# canSlaveV05_testboard.net
KiCad netlist of a schematic drawn in EAGLE
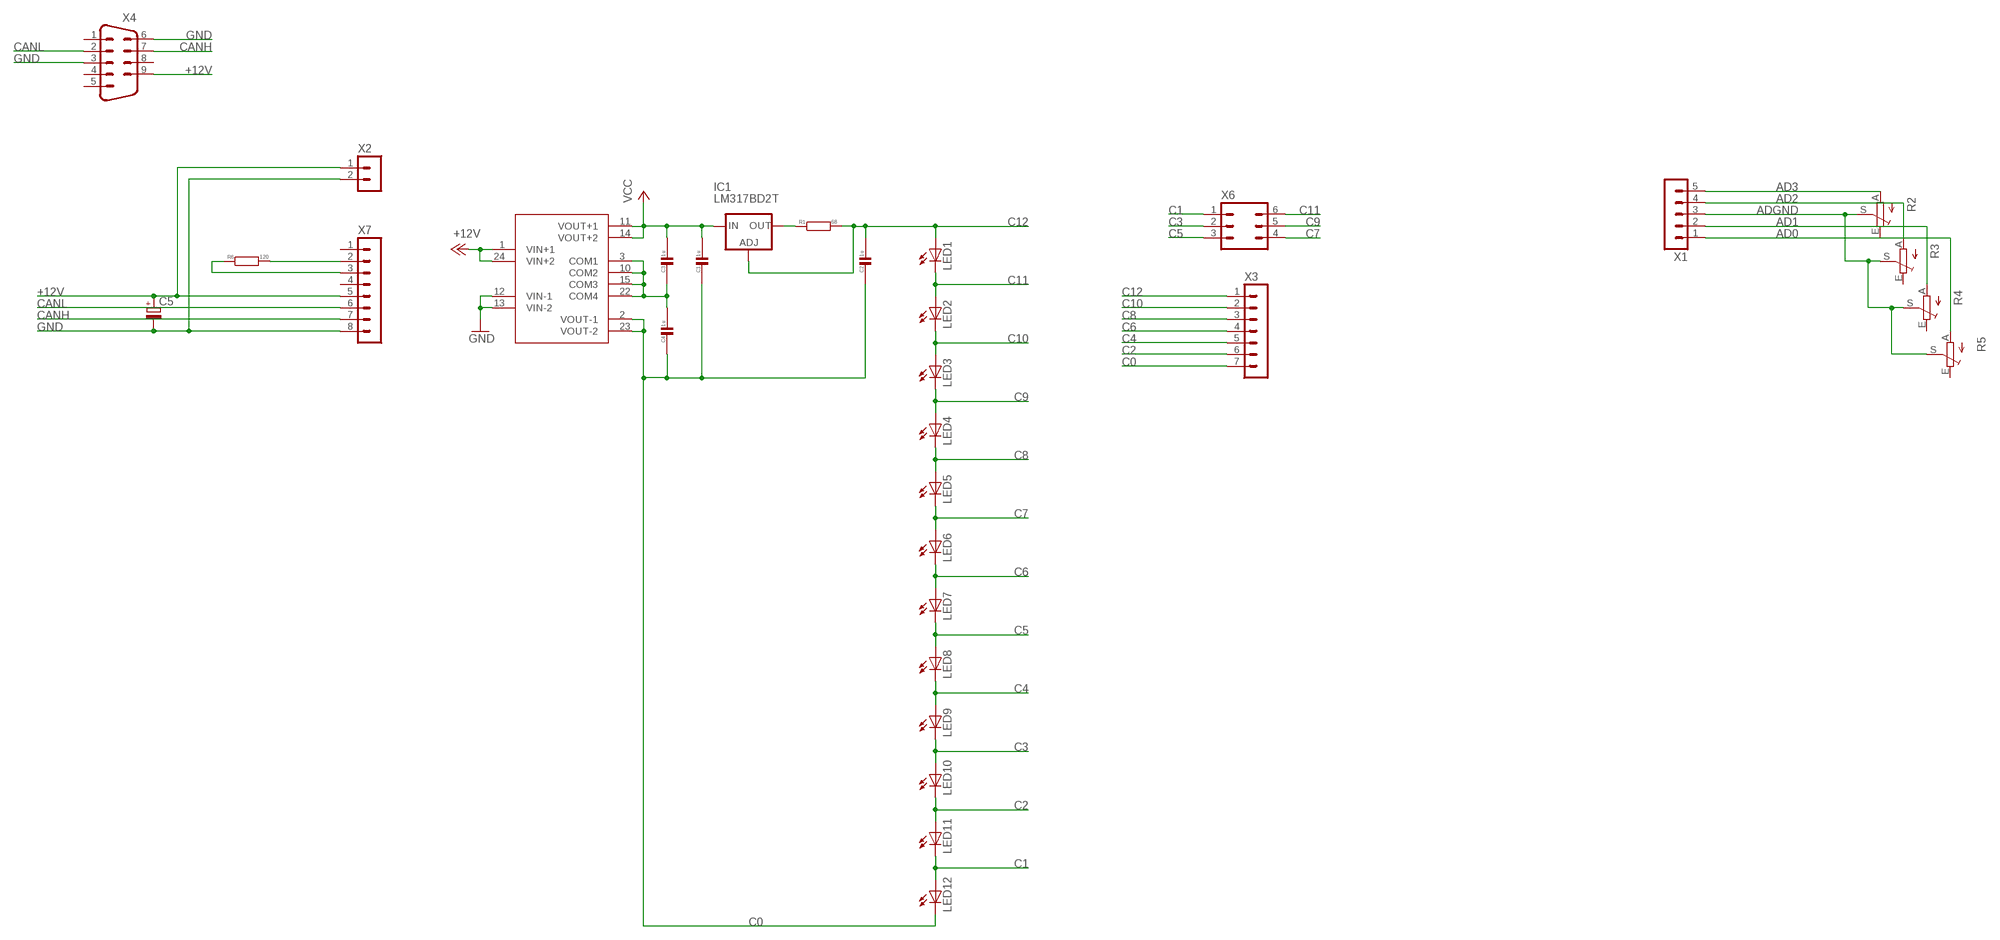
[diagram p0: schematic, sheet 1]

(export (version "E")
  (design (tool "Eeschema 10.0.6"))
  (components
    (comp (ref "C1")
      (value "1u")
      (footprint "eagle-import:C1206")
      (libsource (lib "eagle-import") (part "C1206"))
    )
    (comp (ref "C2")
      (value "1u")
      (footprint "eagle-import:C1206")
      (libsource (lib "eagle-import") (part "C1206"))
    )
    (comp (ref "C3")
      (value "1u")
      (footprint "eagle-import:C1206")
      (libsource (lib "eagle-import") (part "C1206"))
    )
    (comp (ref "C4")
      (value "1u")
      (footprint "eagle-import:C1206")
      (libsource (lib "eagle-import") (part "C1206"))
    )
    (comp (ref "C5")
      (value "CPOL-EUE10-20")
      (footprint "eagle-import:EB20D")
      (libsource (lib "eagle-import") (part "CPOL-EUE10-20"))
    )
    (comp (ref "IC1")
      (value "LM317BD2T")
      (footprint "eagle-import:D2PACK")
      (libsource (lib "eagle-import") (part "LM317?BD2T"))
    )
    (comp (ref "LED1")
      (value "LEDSMT1206")
      (footprint "eagle-import:1206")
      (libsource (lib "eagle-import") (part "LEDSMT1206"))
    )
    (comp (ref "LED2")
      (value "LEDSMT1206")
      (footprint "eagle-import:1206")
      (libsource (lib "eagle-import") (part "LEDSMT1206"))
    )
    (comp (ref "LED3")
      (value "LEDSMT1206")
      (footprint "eagle-import:1206")
      (libsource (lib "eagle-import") (part "LEDSMT1206"))
    )
    (comp (ref "LED4")
      (value "LEDSMT1206")
      (footprint "eagle-import:1206")
      (libsource (lib "eagle-import") (part "LEDSMT1206"))
    )
    (comp (ref "LED5")
      (value "LEDSMT1206")
      (footprint "eagle-import:1206")
      (libsource (lib "eagle-import") (part "LEDSMT1206"))
    )
    (comp (ref "LED6")
      (value "LEDSMT1206")
      (footprint "eagle-import:1206")
      (libsource (lib "eagle-import") (part "LEDSMT1206"))
    )
    (comp (ref "LED7")
      (value "LEDSMT1206")
      (footprint "eagle-import:1206")
      (libsource (lib "eagle-import") (part "LEDSMT1206"))
    )
    (comp (ref "LED8")
      (value "LEDSMT1206")
      (footprint "eagle-import:1206")
      (libsource (lib "eagle-import") (part "LEDSMT1206"))
    )
    (comp (ref "LED9")
      (value "LEDSMT1206")
      (footprint "eagle-import:1206")
      (libsource (lib "eagle-import") (part "LEDSMT1206"))
    )
    (comp (ref "LED10")
      (value "LEDSMT1206")
      (footprint "eagle-import:1206")
      (libsource (lib "eagle-import") (part "LEDSMT1206"))
    )
    (comp (ref "LED11")
      (value "LEDSMT1206")
      (footprint "eagle-import:1206")
      (libsource (lib "eagle-import") (part "LEDSMT1206"))
    )
    (comp (ref "LED12")
      (value "LEDSMT1206")
      (footprint "eagle-import:1206")
      (libsource (lib "eagle-import") (part "LEDSMT1206"))
    )
    (comp (ref "R1")
      (value "68")
      (footprint "eagle-import:R1206")
      (libsource (lib "eagle-import") (part "R1206"))
    )
    (comp (ref "R2")
      (value "TRIM_EU-CIP20C-6MM")
      (footprint "eagle-import:CIP20C-6MM")
      (libsource (lib "eagle-import") (part "TRIM_EU-CIP20C-6MM"))
    )
    (comp (ref "R3")
      (value "TRIM_EU-CIP20C-6MM")
      (footprint "eagle-import:CIP20C-6MM")
      (libsource (lib "eagle-import") (part "TRIM_EU-CIP20C-6MM"))
    )
    (comp (ref "R4")
      (value "TRIM_EU-CIP20C-6MM")
      (footprint "eagle-import:CIP20C-6MM")
      (libsource (lib "eagle-import") (part "TRIM_EU-CIP20C-6MM"))
    )
    (comp (ref "R5")
      (value "TRIM_EU-CIP20C-6MM")
      (footprint "eagle-import:CIP20C-6MM")
      (libsource (lib "eagle-import") (part "TRIM_EU-CIP20C-6MM"))
    )
    (comp (ref "R6")
      (value "120")
      (footprint "eagle-import:R1206")
      (libsource (lib "eagle-import") (part "R1206"))
    )
    (comp (ref "U$1")
      (value "JCB0312D24")
      (footprint "eagle-import:JCB03")
      (libsource (lib "eagle-import") (part "JCB0312D24"))
    )
    (comp (ref "X1")
      (value "HEADER_POS5_43650-0515")
      (footprint "eagle-import:43650-0515")
      (libsource (lib "eagle-import") (part "HEADER_POS5_?43650-0515"))
    )
    (comp (ref "X2")
      (value "HEADER_POS2_43650-0215")
      (footprint "eagle-import:43650-0215")
      (libsource (lib "eagle-import") (part "HEADER_POS2_?43650-0215"))
    )
    (comp (ref "X3")
      (value "HEADER_POS7_43650-0715")
      (footprint "eagle-import:43650-0715")
      (libsource (lib "eagle-import") (part "HEADER_POS7_?43650-0715"))
    )
    (comp (ref "X4")
      (value "M09HP")
      (footprint "eagle-import:M09HP")
      (libsource (lib "eagle-import") (part "M09HP"))
    )
    (comp (ref "X6")
      (value "HEADER_POS6_43650-0615")
      (footprint "eagle-import:43650-0615")
      (libsource (lib "eagle-import") (part "HEADER_POS6_?43650-0615"))
    )
    (comp (ref "X7")
      (value "HEADER_POS8_43045-0812")
      (footprint "eagle-import:43045-0812")
      (libsource (lib "eagle-import") (part "HEADER_POS8_?43045-0812"))
    )
  )
  (nets
    (net (code "1") (name "+12V") (class "Default")
      (node (ref "C5") (pin "+") (pinfunction "+_+") (pintype "passive"))
      (node (ref "U$1") (pin "1") (pinfunction "VIN+1_1") (pintype "bidirectional"))
      (node (ref "U$1") (pin "24") (pinfunction "VIN+2_24") (pintype "bidirectional"))
      (node (ref "X2") (pin "1") (pinfunction "1_1") (pintype "passive"))
      (node (ref "X4") (pin "9") (pinfunction "9_9") (pintype "passive"))
      (node (ref "X7") (pin "5") (pinfunction "5_5") (pintype "passive"))
    )
    (net (code "2") (name "/AD0") (class "Default")
      (node (ref "R5") (pin "A") (pinfunction "A_A") (pintype "passive"))
      (node (ref "X1") (pin "1") (pinfunction "1_1") (pintype "passive"))
    )
    (net (code "3") (name "/AD1") (class "Default")
      (node (ref "R4") (pin "A") (pinfunction "A_A") (pintype "passive"))
      (node (ref "X1") (pin "2") (pinfunction "2_2") (pintype "passive"))
    )
    (net (code "4") (name "/AD2") (class "Default")
      (node (ref "R3") (pin "A") (pinfunction "A_A") (pintype "passive"))
      (node (ref "X1") (pin "4") (pinfunction "4_4") (pintype "passive"))
    )
    (net (code "5") (name "/AD3") (class "Default")
      (node (ref "R2") (pin "A") (pinfunction "A_A") (pintype "passive"))
      (node (ref "X1") (pin "5") (pinfunction "5_5") (pintype "passive"))
    )
    (net (code "6") (name "/ADGND") (class "Default")
      (node (ref "R2") (pin "S") (pinfunction "S_S") (pintype "passive"))
      (node (ref "R3") (pin "S") (pinfunction "S_S") (pintype "passive"))
      (node (ref "R4") (pin "S") (pinfunction "S_S") (pintype "passive"))
      (node (ref "R5") (pin "S") (pinfunction "S_S") (pintype "passive"))
      (node (ref "X1") (pin "3") (pinfunction "3_3") (pintype "passive"))
    )
    (net (code "7") (name "/C0") (class "Default")
      (node (ref "C1") (pin "2") (pinfunction "2_2") (pintype "passive"))
      (node (ref "C2") (pin "2") (pinfunction "2_2") (pintype "passive"))
      (node (ref "C4") (pin "2") (pinfunction "2_2") (pintype "passive"))
      (node (ref "LED12") (pin "C") (pinfunction "C_C") (pintype "passive"))
      (node (ref "U$1") (pin "2") (pinfunction "VOUT-1_2") (pintype "bidirectional"))
      (node (ref "U$1") (pin "23") (pinfunction "VOUT-2_23") (pintype "bidirectional"))
      (node (ref "X3") (pin "7") (pinfunction "7_7") (pintype "passive"))
    )
    (net (code "8") (name "/C1") (class "Default")
      (node (ref "LED11") (pin "C") (pinfunction "C_C") (pintype "passive"))
      (node (ref "LED12") (pin "A") (pinfunction "A_A") (pintype "passive"))
      (node (ref "X6") (pin "1") (pinfunction "1_1") (pintype "passive"))
    )
    (net (code "9") (name "/C2") (class "Default")
      (node (ref "LED10") (pin "C") (pinfunction "C_C") (pintype "passive"))
      (node (ref "LED11") (pin "A") (pinfunction "A_A") (pintype "passive"))
      (node (ref "X3") (pin "6") (pinfunction "6_6") (pintype "passive"))
    )
    (net (code "10") (name "/C3") (class "Default")
      (node (ref "LED10") (pin "A") (pinfunction "A_A") (pintype "passive"))
      (node (ref "LED9") (pin "C") (pinfunction "C_C") (pintype "passive"))
      (node (ref "X6") (pin "2") (pinfunction "2_2") (pintype "passive"))
    )
    (net (code "11") (name "/C4") (class "Default")
      (node (ref "LED8") (pin "C") (pinfunction "C_C") (pintype "passive"))
      (node (ref "LED9") (pin "A") (pinfunction "A_A") (pintype "passive"))
      (node (ref "X3") (pin "5") (pinfunction "5_5") (pintype "passive"))
    )
    (net (code "12") (name "/C5") (class "Default")
      (node (ref "LED7") (pin "C") (pinfunction "C_C") (pintype "passive"))
      (node (ref "LED8") (pin "A") (pinfunction "A_A") (pintype "passive"))
      (node (ref "X6") (pin "3") (pinfunction "3_3") (pintype "passive"))
    )
    (net (code "13") (name "/C6") (class "Default")
      (node (ref "LED6") (pin "C") (pinfunction "C_C") (pintype "passive"))
      (node (ref "LED7") (pin "A") (pinfunction "A_A") (pintype "passive"))
      (node (ref "X3") (pin "4") (pinfunction "4_4") (pintype "passive"))
    )
    (net (code "14") (name "/C7") (class "Default")
      (node (ref "LED5") (pin "C") (pinfunction "C_C") (pintype "passive"))
      (node (ref "LED6") (pin "A") (pinfunction "A_A") (pintype "passive"))
      (node (ref "X6") (pin "4") (pinfunction "4_4") (pintype "passive"))
    )
    (net (code "15") (name "/C8") (class "Default")
      (node (ref "LED4") (pin "C") (pinfunction "C_C") (pintype "passive"))
      (node (ref "LED5") (pin "A") (pinfunction "A_A") (pintype "passive"))
      (node (ref "X3") (pin "3") (pinfunction "3_3") (pintype "passive"))
    )
    (net (code "16") (name "/C9") (class "Default")
      (node (ref "LED3") (pin "C") (pinfunction "C_C") (pintype "passive"))
      (node (ref "LED4") (pin "A") (pinfunction "A_A") (pintype "passive"))
      (node (ref "X6") (pin "5") (pinfunction "5_5") (pintype "passive"))
    )
    (net (code "17") (name "/C10") (class "Default")
      (node (ref "LED2") (pin "C") (pinfunction "C_C") (pintype "passive"))
      (node (ref "LED3") (pin "A") (pinfunction "A_A") (pintype "passive"))
      (node (ref "X3") (pin "2") (pinfunction "2_2") (pintype "passive"))
    )
    (net (code "18") (name "/C11") (class "Default")
      (node (ref "LED1") (pin "C") (pinfunction "C_C") (pintype "passive"))
      (node (ref "LED2") (pin "A") (pinfunction "A_A") (pintype "passive"))
      (node (ref "X6") (pin "6") (pinfunction "6_6") (pintype "passive"))
    )
    (net (code "19") (name "/C12") (class "Default")
      (node (ref "C2") (pin "1") (pinfunction "1_1") (pintype "passive"))
      (node (ref "IC1") (pin "1") (pinfunction "ADJ_1") (pintype "input"))
      (node (ref "LED1") (pin "A") (pinfunction "A_A") (pintype "passive"))
      (node (ref "R1") (pin "2") (pinfunction "2_2") (pintype "passive"))
      (node (ref "X3") (pin "1") (pinfunction "1_1") (pintype "passive"))
    )
    (net (code "20") (name "/CANH") (class "Default")
      (node (ref "X4") (pin "7") (pinfunction "7_7") (pintype "passive"))
      (node (ref "X7") (pin "7") (pinfunction "7_7") (pintype "passive"))
    )
    (net (code "21") (name "/CANL") (class "Default")
      (node (ref "X4") (pin "2") (pinfunction "2_2") (pintype "passive"))
      (node (ref "X7") (pin "6") (pinfunction "6_6") (pintype "passive"))
    )
    (net (code "22") (name "GND") (class "Default")
      (node (ref "C5") (pin "-") (pinfunction "-_-") (pintype "passive"))
      (node (ref "U$1") (pin "12") (pinfunction "VIN-1_12") (pintype "bidirectional"))
      (node (ref "U$1") (pin "13") (pinfunction "VIN-2_13") (pintype "bidirectional"))
      (node (ref "X2") (pin "2") (pinfunction "2_2") (pintype "passive"))
      (node (ref "X4") (pin "3") (pinfunction "3_3") (pintype "passive"))
      (node (ref "X4") (pin "6") (pinfunction "6_6") (pintype "passive"))
      (node (ref "X7") (pin "8") (pinfunction "8_8") (pintype "passive"))
    )
    (net (code "23") (name "Net-(IC1-OUT)") (class "Default")
      (node (ref "IC1") (pin "2") (pinfunction "OUT_2") (pintype "passive"))
      (node (ref "R1") (pin "1") (pinfunction "1_1") (pintype "passive"))
    )
    (net (code "24") (name "Net-(R6-Pad1)") (class "Default")
      (node (ref "R6") (pin "1") (pinfunction "1_1") (pintype "passive"))
      (node (ref "X7") (pin "3") (pinfunction "3_3") (pintype "passive"))
    )
    (net (code "25") (name "Net-(R6-Pad2)") (class "Default")
      (node (ref "R6") (pin "2") (pinfunction "2_2") (pintype "passive"))
      (node (ref "X7") (pin "2") (pinfunction "2_2") (pintype "passive"))
    )
    (net (code "26") (name "Net-(U$1-COM1)") (class "Default")
      (node (ref "C3") (pin "2") (pinfunction "2_2") (pintype "passive"))
      (node (ref "C4") (pin "1") (pinfunction "1_1") (pintype "passive"))
      (node (ref "U$1") (pin "10") (pinfunction "COM2_10") (pintype "bidirectional"))
      (node (ref "U$1") (pin "15") (pinfunction "COM3_15") (pintype "bidirectional"))
      (node (ref "U$1") (pin "22") (pinfunction "COM4_22") (pintype "bidirectional"))
      (node (ref "U$1") (pin "3") (pinfunction "COM1_3") (pintype "bidirectional"))
    )
    (net (code "27") (name "VCC") (class "Default")
      (node (ref "C1") (pin "1") (pinfunction "1_1") (pintype "passive"))
      (node (ref "C3") (pin "1") (pinfunction "1_1") (pintype "passive"))
      (node (ref "IC1") (pin "3") (pinfunction "IN_3") (pintype "input"))
      (node (ref "U$1") (pin "11") (pinfunction "VOUT+1_11") (pintype "bidirectional"))
      (node (ref "U$1") (pin "14") (pinfunction "VOUT+2_14") (pintype "bidirectional"))
    )
    (net (code "28") (name "unconnected-(R2-PadE)") (class "Default")
      (node (ref "R2") (pin "E") (pinfunction "E_E") (pintype "passive"))
    )
    (net (code "29") (name "unconnected-(R3-PadE)") (class "Default")
      (node (ref "R3") (pin "E") (pinfunction "E_E") (pintype "passive"))
    )
    (net (code "30") (name "unconnected-(R4-PadE)") (class "Default")
      (node (ref "R4") (pin "E") (pinfunction "E_E") (pintype "passive"))
    )
    (net (code "31") (name "unconnected-(R5-PadE)") (class "Default")
      (node (ref "R5") (pin "E") (pinfunction "E_E") (pintype "passive"))
    )
    (net (code "32") (name "unconnected-(X4-Pad1)") (class "Default")
      (node (ref "X4") (pin "1") (pinfunction "1_1") (pintype "passive"))
    )
    (net (code "33") (name "unconnected-(X4-Pad4)") (class "Default")
      (node (ref "X4") (pin "4") (pinfunction "4_4") (pintype "passive"))
    )
    (net (code "34") (name "unconnected-(X4-Pad5)") (class "Default")
      (node (ref "X4") (pin "5") (pinfunction "5_5") (pintype "passive"))
    )
    (net (code "35") (name "unconnected-(X4-Pad8)") (class "Default")
      (node (ref "X4") (pin "8") (pinfunction "8_8") (pintype "passive"))
    )
    (net (code "36") (name "unconnected-(X7-Pad1)") (class "Default")
      (node (ref "X7") (pin "1") (pinfunction "1_1") (pintype "passive"))
    )
    (net (code "37") (name "unconnected-(X7-Pad4)") (class "Default")
      (node (ref "X7") (pin "4") (pinfunction "4_4") (pintype "passive"))
    )
  )
)
